# Backplane_Reference.net
KiCad netlist of a schematic drawn in EAGLE
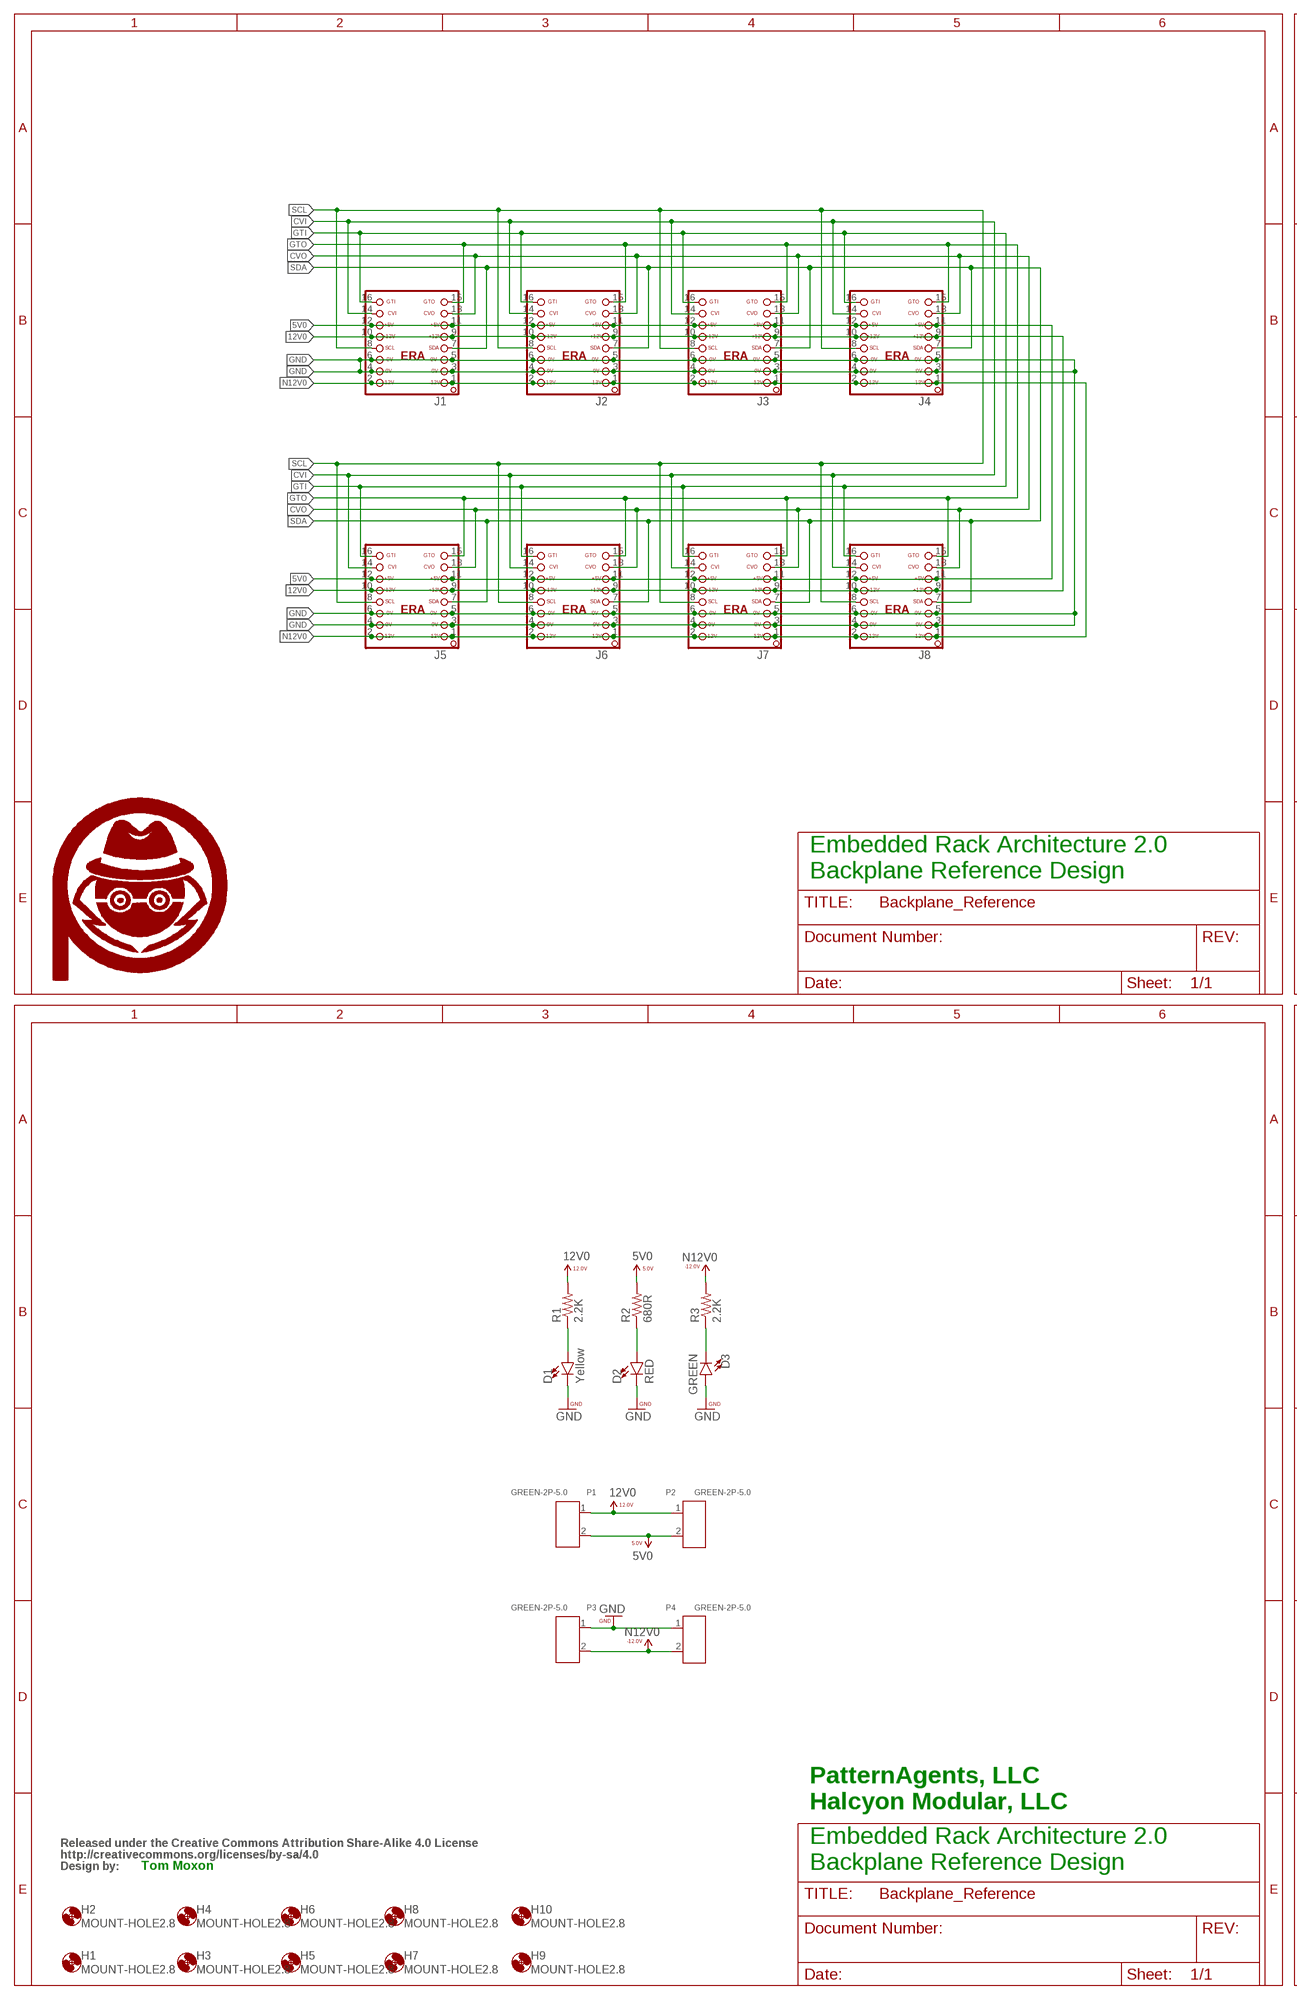
[diagram p0: schematic, sheet 1, part 1 of 2]
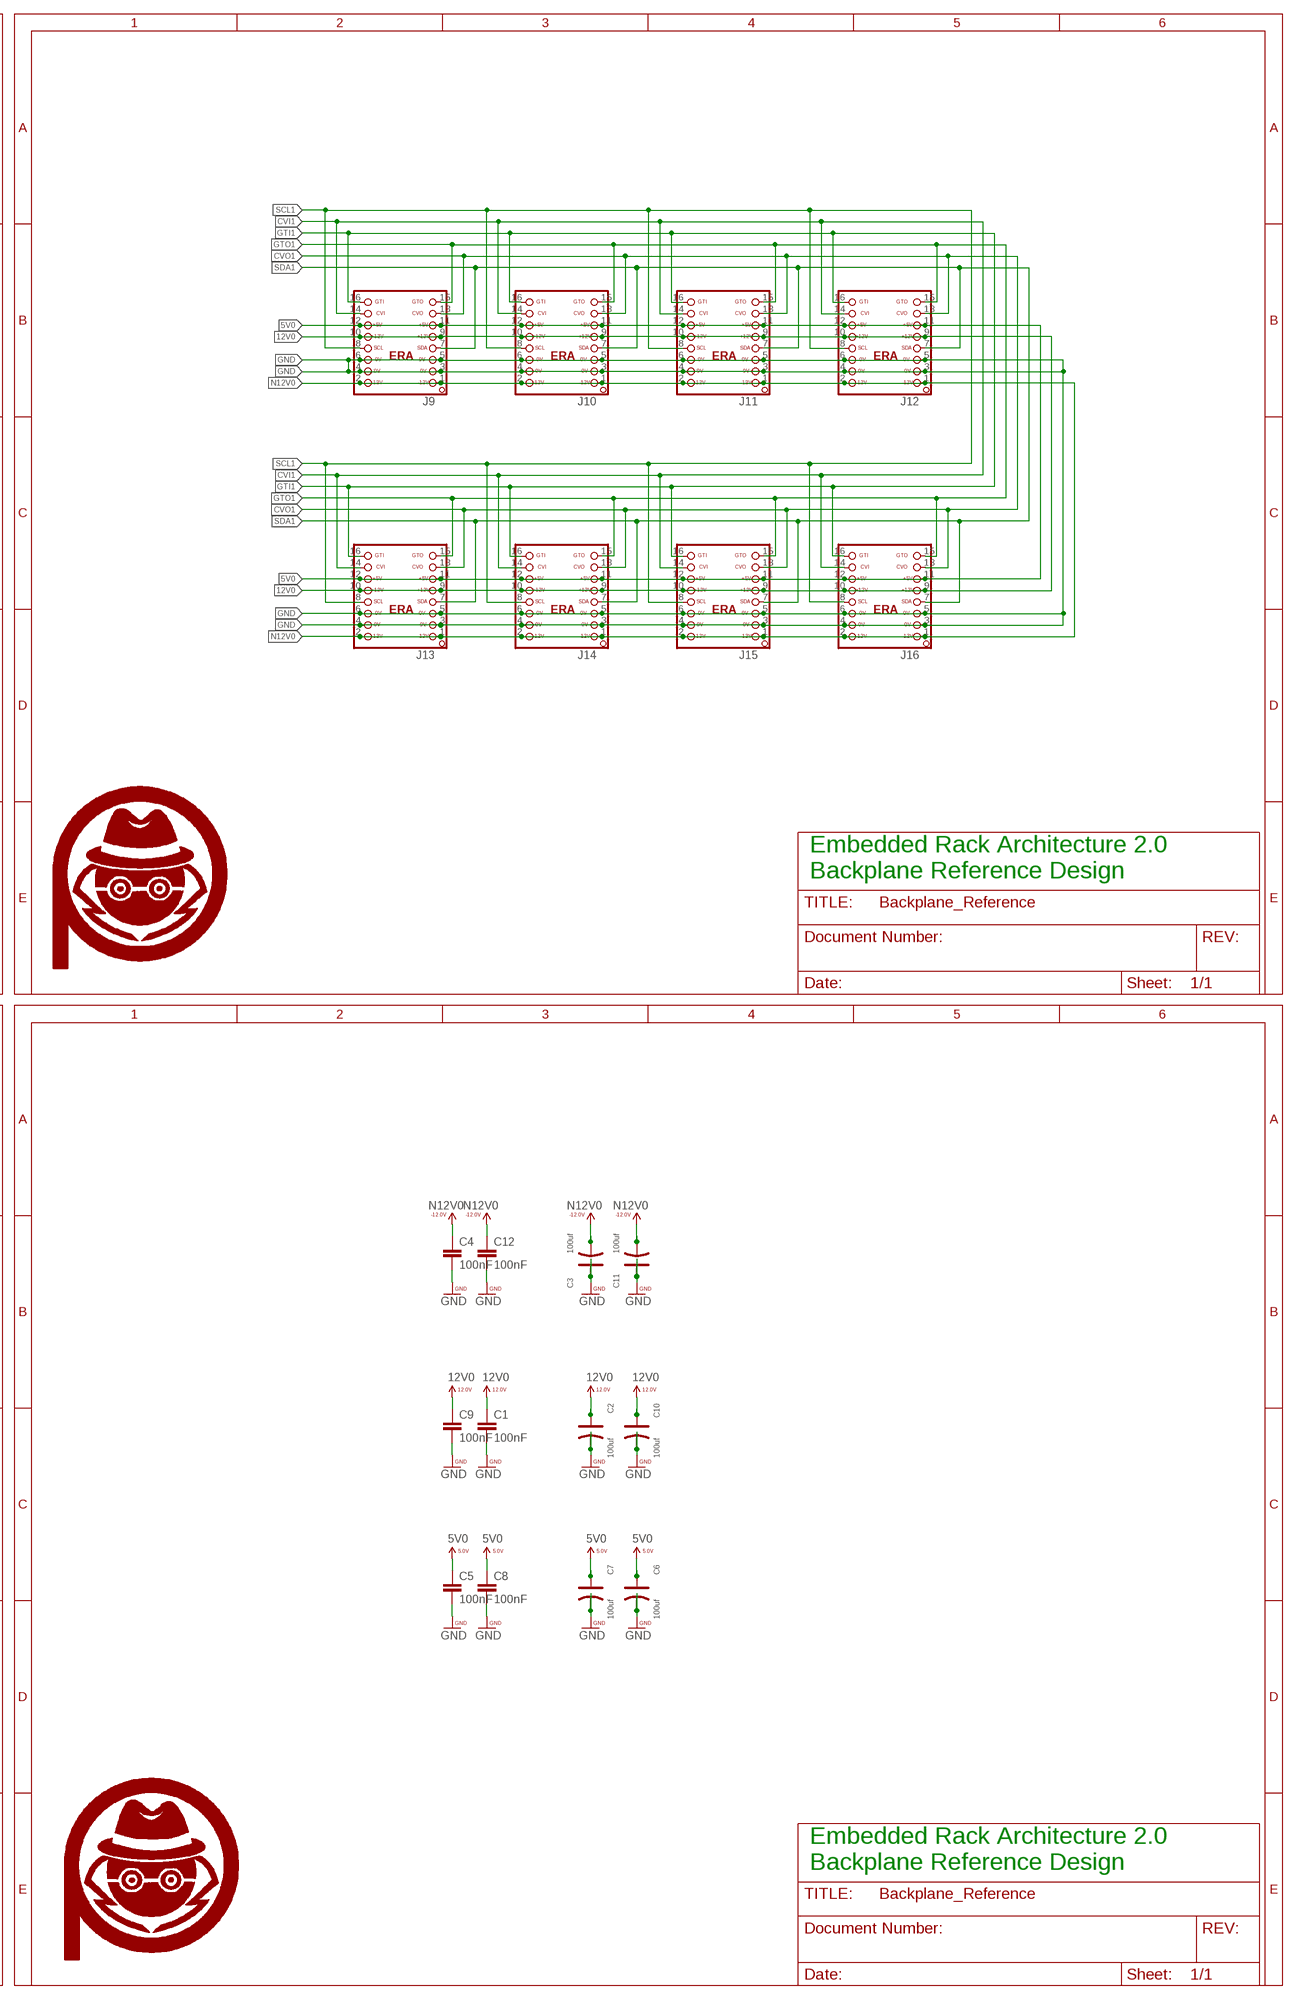
[diagram p1: schematic, sheet 1, part 2 of 2]

(export (version "E")
  (design (tool "Eeschema 10.0.6"))
  (components
    (comp (ref "C1")
      (value "100nF")
      (footprint "eagle-import:0603-CAP")
      (libsource (lib "eagle-import") (part "CAP0603-CAP"))
    )
    (comp (ref "C2")
      (value "100uf")
      (footprint "eagle-import:PC-D5.3MM")
      (fields (field (name "MPN") "KS 100uF/16V"))
      (libsource (lib "eagle-import") (part "DIP-ALUMINUM-100UF-16V(D5-H7MM)"))
    )
    (comp (ref "C3")
      (value "100uf")
      (footprint "eagle-import:PC-D5.3MM")
      (fields (field (name "MPN") "KS 100uF/16V"))
      (libsource (lib "eagle-import") (part "DIP-ALUMINUM-100UF-16V(D5-H7MM)"))
    )
    (comp (ref "C4")
      (value "100nF")
      (footprint "eagle-import:0603-CAP")
      (libsource (lib "eagle-import") (part "CAP0603-CAP"))
    )
    (comp (ref "C5")
      (value "100nF")
      (footprint "eagle-import:0603-CAP")
      (libsource (lib "eagle-import") (part "CAP0603-CAP"))
    )
    (comp (ref "C6")
      (value "100uf")
      (footprint "eagle-import:PC-D5.3MM")
      (fields (field (name "MPN") "KS 100uF/16V"))
      (libsource (lib "eagle-import") (part "DIP-ALUMINUM-100UF-16V(D5-H7MM)"))
    )
    (comp (ref "C7")
      (value "100uf")
      (footprint "eagle-import:PC-D5.3MM")
      (fields (field (name "MPN") "KS 100uF/16V"))
      (libsource (lib "eagle-import") (part "DIP-ALUMINUM-100UF-16V(D5-H7MM)"))
    )
    (comp (ref "C8")
      (value "100nF")
      (footprint "eagle-import:0603-CAP")
      (libsource (lib "eagle-import") (part "CAP0603-CAP"))
    )
    (comp (ref "C9")
      (value "100nF")
      (footprint "eagle-import:0603-CAP")
      (libsource (lib "eagle-import") (part "CAP0603-CAP"))
    )
    (comp (ref "C10")
      (value "100uf")
      (footprint "eagle-import:PC-D5.3MM")
      (fields (field (name "MPN") "KS 100uF/16V"))
      (libsource (lib "eagle-import") (part "DIP-ALUMINUM-100UF-16V(D5-H7MM)"))
    )
    (comp (ref "C11")
      (value "100uf")
      (footprint "eagle-import:PC-D5.3MM")
      (fields (field (name "MPN") "KS 100uF/16V"))
      (libsource (lib "eagle-import") (part "DIP-ALUMINUM-100UF-16V(D5-H7MM)"))
    )
    (comp (ref "C12")
      (value "100nF")
      (footprint "eagle-import:0603-CAP")
      (libsource (lib "eagle-import") (part "CAP0603-CAP"))
    )
    (comp (ref "D1")
      (value "Yellow")
      (footprint "eagle-import:LED-0603")
      (libsource (lib "eagle-import") (part "LED-YELLOW0603"))
    )
    (comp (ref "D2")
      (value "RED")
      (footprint "eagle-import:LED-0603")
      (libsource (lib "eagle-import") (part "LED-RED0603"))
    )
    (comp (ref "D3")
      (value "GREEN")
      (footprint "eagle-import:LED-0603")
      (libsource (lib "eagle-import") (part "LED-GREEN0603"))
    )
    (comp (ref "H1")
      (value "MOUNT-HOLE2.8")
      (footprint "eagle-import:2,8")
      (libsource (lib "eagle-import") (part "MOUNT-HOLE2.8"))
    )
    (comp (ref "H2")
      (value "MOUNT-HOLE2.8")
      (footprint "eagle-import:2,8")
      (libsource (lib "eagle-import") (part "MOUNT-HOLE2.8"))
    )
    (comp (ref "H3")
      (value "MOUNT-HOLE2.8")
      (footprint "eagle-import:2,8")
      (libsource (lib "eagle-import") (part "MOUNT-HOLE2.8"))
    )
    (comp (ref "H4")
      (value "MOUNT-HOLE2.8")
      (footprint "eagle-import:2,8")
      (libsource (lib "eagle-import") (part "MOUNT-HOLE2.8"))
    )
    (comp (ref "H5")
      (value "MOUNT-HOLE2.8")
      (footprint "eagle-import:2,8")
      (libsource (lib "eagle-import") (part "MOUNT-HOLE2.8"))
    )
    (comp (ref "H6")
      (value "MOUNT-HOLE2.8")
      (footprint "eagle-import:2,8")
      (libsource (lib "eagle-import") (part "MOUNT-HOLE2.8"))
    )
    (comp (ref "H7")
      (value "MOUNT-HOLE2.8")
      (footprint "eagle-import:2,8")
      (libsource (lib "eagle-import") (part "MOUNT-HOLE2.8"))
    )
    (comp (ref "H8")
      (value "MOUNT-HOLE2.8")
      (footprint "eagle-import:2,8")
      (libsource (lib "eagle-import") (part "MOUNT-HOLE2.8"))
    )
    (comp (ref "H9")
      (value "MOUNT-HOLE2.8")
      (footprint "eagle-import:2,8")
      (libsource (lib "eagle-import") (part "MOUNT-HOLE2.8"))
    )
    (comp (ref "H10")
      (value "MOUNT-HOLE2.8")
      (footprint "eagle-import:2,8")
      (libsource (lib "eagle-import") (part "MOUNT-HOLE2.8"))
    )
    (comp (ref "J1")
      (value "ERA-SHROUD")
      (footprint "eagle-import:ERA")
      (libsource (lib "eagle-import") (part "ERA-SHROUD"))
    )
    (comp (ref "J2")
      (value "ERA-SHROUD")
      (footprint "eagle-import:ERA")
      (libsource (lib "eagle-import") (part "ERA-SHROUD"))
    )
    (comp (ref "J3")
      (value "ERA-SHROUD")
      (footprint "eagle-import:ERA")
      (libsource (lib "eagle-import") (part "ERA-SHROUD"))
    )
    (comp (ref "J4")
      (value "ERA-SHROUD")
      (footprint "eagle-import:ERA")
      (libsource (lib "eagle-import") (part "ERA-SHROUD"))
    )
    (comp (ref "J5")
      (value "ERA-SHROUD")
      (footprint "eagle-import:ERA")
      (libsource (lib "eagle-import") (part "ERA-SHROUD"))
    )
    (comp (ref "J6")
      (value "ERA-SHROUD")
      (footprint "eagle-import:ERA")
      (libsource (lib "eagle-import") (part "ERA-SHROUD"))
    )
    (comp (ref "J7")
      (value "ERA-SHROUD")
      (footprint "eagle-import:ERA")
      (libsource (lib "eagle-import") (part "ERA-SHROUD"))
    )
    (comp (ref "J8")
      (value "ERA-SHROUD")
      (footprint "eagle-import:ERA")
      (libsource (lib "eagle-import") (part "ERA-SHROUD"))
    )
    (comp (ref "J9")
      (value "ERA-SHROUD")
      (footprint "eagle-import:ERA")
      (libsource (lib "eagle-import") (part "ERA-SHROUD"))
    )
    (comp (ref "J10")
      (value "ERA-SHROUD")
      (footprint "eagle-import:ERA")
      (libsource (lib "eagle-import") (part "ERA-SHROUD"))
    )
    (comp (ref "J11")
      (value "ERA-SHROUD")
      (footprint "eagle-import:ERA")
      (libsource (lib "eagle-import") (part "ERA-SHROUD"))
    )
    (comp (ref "J12")
      (value "ERA-SHROUD")
      (footprint "eagle-import:ERA")
      (libsource (lib "eagle-import") (part "ERA-SHROUD"))
    )
    (comp (ref "J13")
      (value "ERA-SHROUD")
      (footprint "eagle-import:ERA")
      (libsource (lib "eagle-import") (part "ERA-SHROUD"))
    )
    (comp (ref "J14")
      (value "ERA-SHROUD")
      (footprint "eagle-import:ERA")
      (libsource (lib "eagle-import") (part "ERA-SHROUD"))
    )
    (comp (ref "J15")
      (value "ERA-SHROUD")
      (footprint "eagle-import:ERA")
      (libsource (lib "eagle-import") (part "ERA-SHROUD"))
    )
    (comp (ref "J16")
      (value "ERA-SHROUD")
      (footprint "eagle-import:ERA")
      (libsource (lib "eagle-import") (part "ERA-SHROUD"))
    )
    (comp (ref "P1")
      (value "GREEN-2P-5.0")
      (footprint "eagle-import:H2-5.0-10.5X8.0MM")
      (libsource (lib "eagle-import") (part "SCREW-TERMINAL-GREEN(2P-5.0)"))
    )
    (comp (ref "P2")
      (value "GREEN-2P-5.0")
      (footprint "eagle-import:H2-5.0-10.5X8.0MM")
      (libsource (lib "eagle-import") (part "SCREW-TERMINAL-GREEN(2P-5.0)"))
    )
    (comp (ref "P3")
      (value "GREEN-2P-5.0")
      (footprint "eagle-import:H2-5.0-10.5X8.0MM")
      (libsource (lib "eagle-import") (part "SCREW-TERMINAL-GREEN(2P-5.0)"))
    )
    (comp (ref "P4")
      (value "GREEN-2P-5.0")
      (footprint "eagle-import:H2-5.0-10.5X8.0MM")
      (libsource (lib "eagle-import") (part "SCREW-TERMINAL-GREEN(2P-5.0)"))
    )
    (comp (ref "R1")
      (value "2.2K")
      (footprint "eagle-import:0603-RES")
      (libsource (lib "eagle-import") (part "RESISTOR0603"))
    )
    (comp (ref "R2")
      (value "680R")
      (footprint "eagle-import:0603-RES")
      (libsource (lib "eagle-import") (part "RESISTOR0603"))
    )
    (comp (ref "R3")
      (value "2.2K")
      (footprint "eagle-import:0603-RES")
      (libsource (lib "eagle-import") (part "RESISTOR0603"))
    )
    (comp (ref "U$19")
      (value "PA_LOGO_SYMMED")
      (footprint "eagle-import:PA_LOGO_AGENT_MED_SYM")
      (libsource (lib "eagle-import") (part "PA_LOGO_SYMMED"))
    )
    (comp (ref "U$37")
      (value "PA_LOGO_SYMMED")
      (footprint "eagle-import:PA_LOGO_AGENT_MED_SYM")
      (libsource (lib "eagle-import") (part "PA_LOGO_SYMMED"))
    )
    (comp (ref "U$38")
      (value "PA_LOGO_SYMLARGE")
      (footprint "eagle-import:PA_LOGO_AGENT_LRG_SYM")
      (libsource (lib "eagle-import") (part "PA_LOGO_SYMLARGE"))
    )
    (comp (ref "U$48")
      (value "BY_CC_SA_TEXTTEXT")
      (footprint "eagle-import:BY_CC_SA_TEXT")
      (libsource (lib "eagle-import") (part "BY_CC_SA_TEXTTEXT"))
    )
  )
  (nets
    (net (code "1") (name "5V0") (class "Default")
      (node (ref "C5") (pin "1") (pinfunction "1_1") (pintype "passive"))
      (node (ref "C6") (pin "+") (pinfunction "+_+") (pintype "passive"))
      (node (ref "C7") (pin "+") (pinfunction "+_+") (pintype "passive"))
      (node (ref "C8") (pin "1") (pinfunction "1_1") (pintype "passive"))
      (node (ref "J1") (pin "11") (pinfunction "11_11") (pintype "passive"))
      (node (ref "J1") (pin "12") (pinfunction "12_12") (pintype "passive"))
      (node (ref "J10") (pin "11") (pinfunction "11_11") (pintype "passive"))
      (node (ref "J10") (pin "12") (pinfunction "12_12") (pintype "passive"))
      (node (ref "J11") (pin "11") (pinfunction "11_11") (pintype "passive"))
      (node (ref "J11") (pin "12") (pinfunction "12_12") (pintype "passive"))
      (node (ref "J12") (pin "11") (pinfunction "11_11") (pintype "passive"))
      (node (ref "J12") (pin "12") (pinfunction "12_12") (pintype "passive"))
      (node (ref "J13") (pin "11") (pinfunction "11_11") (pintype "passive"))
      (node (ref "J13") (pin "12") (pinfunction "12_12") (pintype "passive"))
      (node (ref "J14") (pin "11") (pinfunction "11_11") (pintype "passive"))
      (node (ref "J14") (pin "12") (pinfunction "12_12") (pintype "passive"))
      (node (ref "J15") (pin "11") (pinfunction "11_11") (pintype "passive"))
      (node (ref "J15") (pin "12") (pinfunction "12_12") (pintype "passive"))
      (node (ref "J16") (pin "11") (pinfunction "11_11") (pintype "passive"))
      (node (ref "J16") (pin "12") (pinfunction "12_12") (pintype "passive"))
      (node (ref "J2") (pin "11") (pinfunction "11_11") (pintype "passive"))
      (node (ref "J2") (pin "12") (pinfunction "12_12") (pintype "passive"))
      (node (ref "J3") (pin "11") (pinfunction "11_11") (pintype "passive"))
      (node (ref "J3") (pin "12") (pinfunction "12_12") (pintype "passive"))
      (node (ref "J4") (pin "11") (pinfunction "11_11") (pintype "passive"))
      (node (ref "J4") (pin "12") (pinfunction "12_12") (pintype "passive"))
      (node (ref "J5") (pin "11") (pinfunction "11_11") (pintype "passive"))
      (node (ref "J5") (pin "12") (pinfunction "12_12") (pintype "passive"))
      (node (ref "J6") (pin "11") (pinfunction "11_11") (pintype "passive"))
      (node (ref "J6") (pin "12") (pinfunction "12_12") (pintype "passive"))
      (node (ref "J7") (pin "11") (pinfunction "11_11") (pintype "passive"))
      (node (ref "J7") (pin "12") (pinfunction "12_12") (pintype "passive"))
      (node (ref "J8") (pin "11") (pinfunction "11_11") (pintype "passive"))
      (node (ref "J8") (pin "12") (pinfunction "12_12") (pintype "passive"))
      (node (ref "J9") (pin "11") (pinfunction "11_11") (pintype "passive"))
      (node (ref "J9") (pin "12") (pinfunction "12_12") (pintype "passive"))
      (node (ref "P1") (pin "2") (pinfunction "2_2") (pintype "bidirectional"))
      (node (ref "P2") (pin "2") (pinfunction "2_2") (pintype "bidirectional"))
      (node (ref "R2") (pin "2") (pinfunction "2_2") (pintype "passive"))
    )
    (net (code "2") (name "12V0") (class "Default")
      (node (ref "C1") (pin "1") (pinfunction "1_1") (pintype "passive"))
      (node (ref "C10") (pin "+") (pinfunction "+_+") (pintype "passive"))
      (node (ref "C2") (pin "+") (pinfunction "+_+") (pintype "passive"))
      (node (ref "C9") (pin "1") (pinfunction "1_1") (pintype "passive"))
      (node (ref "J1") (pin "10") (pinfunction "10_10") (pintype "passive"))
      (node (ref "J1") (pin "9") (pinfunction "9_9") (pintype "passive"))
      (node (ref "J10") (pin "10") (pinfunction "10_10") (pintype "passive"))
      (node (ref "J10") (pin "9") (pinfunction "9_9") (pintype "passive"))
      (node (ref "J11") (pin "10") (pinfunction "10_10") (pintype "passive"))
      (node (ref "J11") (pin "9") (pinfunction "9_9") (pintype "passive"))
      (node (ref "J12") (pin "10") (pinfunction "10_10") (pintype "passive"))
      (node (ref "J12") (pin "9") (pinfunction "9_9") (pintype "passive"))
      (node (ref "J13") (pin "10") (pinfunction "10_10") (pintype "passive"))
      (node (ref "J13") (pin "9") (pinfunction "9_9") (pintype "passive"))
      (node (ref "J14") (pin "10") (pinfunction "10_10") (pintype "passive"))
      (node (ref "J14") (pin "9") (pinfunction "9_9") (pintype "passive"))
      (node (ref "J15") (pin "10") (pinfunction "10_10") (pintype "passive"))
      (node (ref "J15") (pin "9") (pinfunction "9_9") (pintype "passive"))
      (node (ref "J16") (pin "10") (pinfunction "10_10") (pintype "passive"))
      (node (ref "J16") (pin "9") (pinfunction "9_9") (pintype "passive"))
      (node (ref "J2") (pin "10") (pinfunction "10_10") (pintype "passive"))
      (node (ref "J2") (pin "9") (pinfunction "9_9") (pintype "passive"))
      (node (ref "J3") (pin "10") (pinfunction "10_10") (pintype "passive"))
      (node (ref "J3") (pin "9") (pinfunction "9_9") (pintype "passive"))
      (node (ref "J4") (pin "10") (pinfunction "10_10") (pintype "passive"))
      (node (ref "J4") (pin "9") (pinfunction "9_9") (pintype "passive"))
      (node (ref "J5") (pin "10") (pinfunction "10_10") (pintype "passive"))
      (node (ref "J5") (pin "9") (pinfunction "9_9") (pintype "passive"))
      (node (ref "J6") (pin "10") (pinfunction "10_10") (pintype "passive"))
      (node (ref "J6") (pin "9") (pinfunction "9_9") (pintype "passive"))
      (node (ref "J7") (pin "10") (pinfunction "10_10") (pintype "passive"))
      (node (ref "J7") (pin "9") (pinfunction "9_9") (pintype "passive"))
      (node (ref "J8") (pin "10") (pinfunction "10_10") (pintype "passive"))
      (node (ref "J8") (pin "9") (pinfunction "9_9") (pintype "passive"))
      (node (ref "J9") (pin "10") (pinfunction "10_10") (pintype "passive"))
      (node (ref "J9") (pin "9") (pinfunction "9_9") (pintype "passive"))
      (node (ref "P1") (pin "1") (pinfunction "1_1") (pintype "bidirectional"))
      (node (ref "P2") (pin "1") (pinfunction "1_1") (pintype "bidirectional"))
      (node (ref "R1") (pin "2") (pinfunction "2_2") (pintype "passive"))
    )
    (net (code "3") (name "CVI") (class "Default")
      (node (ref "J1") (pin "14") (pinfunction "14_14") (pintype "passive"))
      (node (ref "J2") (pin "14") (pinfunction "14_14") (pintype "passive"))
      (node (ref "J3") (pin "14") (pinfunction "14_14") (pintype "passive"))
      (node (ref "J4") (pin "14") (pinfunction "14_14") (pintype "passive"))
      (node (ref "J5") (pin "14") (pinfunction "14_14") (pintype "passive"))
      (node (ref "J6") (pin "14") (pinfunction "14_14") (pintype "passive"))
      (node (ref "J7") (pin "14") (pinfunction "14_14") (pintype "passive"))
      (node (ref "J8") (pin "14") (pinfunction "14_14") (pintype "passive"))
    )
    (net (code "4") (name "CVI1") (class "Default")
      (node (ref "J10") (pin "14") (pinfunction "14_14") (pintype "passive"))
      (node (ref "J11") (pin "14") (pinfunction "14_14") (pintype "passive"))
      (node (ref "J12") (pin "14") (pinfunction "14_14") (pintype "passive"))
      (node (ref "J13") (pin "14") (pinfunction "14_14") (pintype "passive"))
      (node (ref "J14") (pin "14") (pinfunction "14_14") (pintype "passive"))
      (node (ref "J15") (pin "14") (pinfunction "14_14") (pintype "passive"))
      (node (ref "J16") (pin "14") (pinfunction "14_14") (pintype "passive"))
      (node (ref "J9") (pin "14") (pinfunction "14_14") (pintype "passive"))
    )
    (net (code "5") (name "CVO") (class "Default")
      (node (ref "J1") (pin "13") (pinfunction "13_13") (pintype "passive"))
      (node (ref "J2") (pin "13") (pinfunction "13_13") (pintype "passive"))
      (node (ref "J3") (pin "13") (pinfunction "13_13") (pintype "passive"))
      (node (ref "J4") (pin "13") (pinfunction "13_13") (pintype "passive"))
      (node (ref "J5") (pin "13") (pinfunction "13_13") (pintype "passive"))
      (node (ref "J6") (pin "13") (pinfunction "13_13") (pintype "passive"))
      (node (ref "J7") (pin "13") (pinfunction "13_13") (pintype "passive"))
      (node (ref "J8") (pin "13") (pinfunction "13_13") (pintype "passive"))
    )
    (net (code "6") (name "CVO1") (class "Default")
      (node (ref "J10") (pin "13") (pinfunction "13_13") (pintype "passive"))
      (node (ref "J11") (pin "13") (pinfunction "13_13") (pintype "passive"))
      (node (ref "J12") (pin "13") (pinfunction "13_13") (pintype "passive"))
      (node (ref "J13") (pin "13") (pinfunction "13_13") (pintype "passive"))
      (node (ref "J14") (pin "13") (pinfunction "13_13") (pintype "passive"))
      (node (ref "J15") (pin "13") (pinfunction "13_13") (pintype "passive"))
      (node (ref "J16") (pin "13") (pinfunction "13_13") (pintype "passive"))
      (node (ref "J9") (pin "13") (pinfunction "13_13") (pintype "passive"))
    )
    (net (code "7") (name "GND") (class "Default")
      (node (ref "C1") (pin "2") (pinfunction "2_2") (pintype "passive"))
      (node (ref "C10") (pin "-") (pinfunction "-_-") (pintype "passive"))
      (node (ref "C11") (pin "+") (pinfunction "+_+") (pintype "passive"))
      (node (ref "C12") (pin "2") (pinfunction "2_2") (pintype "passive"))
      (node (ref "C2") (pin "-") (pinfunction "-_-") (pintype "passive"))
      (node (ref "C3") (pin "+") (pinfunction "+_+") (pintype "passive"))
      (node (ref "C4") (pin "2") (pinfunction "2_2") (pintype "passive"))
      (node (ref "C5") (pin "2") (pinfunction "2_2") (pintype "passive"))
      (node (ref "C6") (pin "-") (pinfunction "-_-") (pintype "passive"))
      (node (ref "C7") (pin "-") (pinfunction "-_-") (pintype "passive"))
      (node (ref "C8") (pin "2") (pinfunction "2_2") (pintype "passive"))
      (node (ref "C9") (pin "2") (pinfunction "2_2") (pintype "passive"))
      (node (ref "D1") (pin "C") (pinfunction "C_C") (pintype "passive"))
      (node (ref "D2") (pin "C") (pinfunction "C_C") (pintype "passive"))
      (node (ref "D3") (pin "A") (pinfunction "A_A") (pintype "passive"))
      (node (ref "J1") (pin "3") (pinfunction "3_3") (pintype "passive"))
      (node (ref "J1") (pin "4") (pinfunction "4_4") (pintype "passive"))
      (node (ref "J1") (pin "5") (pinfunction "5_5") (pintype "passive"))
      (node (ref "J1") (pin "6") (pinfunction "6_6") (pintype "passive"))
      (node (ref "J10") (pin "3") (pinfunction "3_3") (pintype "passive"))
      (node (ref "J10") (pin "4") (pinfunction "4_4") (pintype "passive"))
      (node (ref "J10") (pin "5") (pinfunction "5_5") (pintype "passive"))
      (node (ref "J10") (pin "6") (pinfunction "6_6") (pintype "passive"))
      (node (ref "J11") (pin "3") (pinfunction "3_3") (pintype "passive"))
      (node (ref "J11") (pin "4") (pinfunction "4_4") (pintype "passive"))
      (node (ref "J11") (pin "5") (pinfunction "5_5") (pintype "passive"))
      (node (ref "J11") (pin "6") (pinfunction "6_6") (pintype "passive"))
      (node (ref "J12") (pin "3") (pinfunction "3_3") (pintype "passive"))
      (node (ref "J12") (pin "4") (pinfunction "4_4") (pintype "passive"))
      (node (ref "J12") (pin "5") (pinfunction "5_5") (pintype "passive"))
      (node (ref "J12") (pin "6") (pinfunction "6_6") (pintype "passive"))
      (node (ref "J13") (pin "3") (pinfunction "3_3") (pintype "passive"))
      (node (ref "J13") (pin "4") (pinfunction "4_4") (pintype "passive"))
      (node (ref "J13") (pin "5") (pinfunction "5_5") (pintype "passive"))
      (node (ref "J13") (pin "6") (pinfunction "6_6") (pintype "passive"))
      (node (ref "J14") (pin "3") (pinfunction "3_3") (pintype "passive"))
      (node (ref "J14") (pin "4") (pinfunction "4_4") (pintype "passive"))
      (node (ref "J14") (pin "5") (pinfunction "5_5") (pintype "passive"))
      (node (ref "J14") (pin "6") (pinfunction "6_6") (pintype "passive"))
      (node (ref "J15") (pin "3") (pinfunction "3_3") (pintype "passive"))
      (node (ref "J15") (pin "4") (pinfunction "4_4") (pintype "passive"))
      (node (ref "J15") (pin "5") (pinfunction "5_5") (pintype "passive"))
      (node (ref "J15") (pin "6") (pinfunction "6_6") (pintype "passive"))
      (node (ref "J16") (pin "3") (pinfunction "3_3") (pintype "passive"))
      (node (ref "J16") (pin "4") (pinfunction "4_4") (pintype "passive"))
      (node (ref "J16") (pin "5") (pinfunction "5_5") (pintype "passive"))
      (node (ref "J16") (pin "6") (pinfunction "6_6") (pintype "passive"))
      (node (ref "J2") (pin "3") (pinfunction "3_3") (pintype "passive"))
      (node (ref "J2") (pin "4") (pinfunction "4_4") (pintype "passive"))
      (node (ref "J2") (pin "5") (pinfunction "5_5") (pintype "passive"))
      (node (ref "J2") (pin "6") (pinfunction "6_6") (pintype "passive"))
      (node (ref "J3") (pin "3") (pinfunction "3_3") (pintype "passive"))
      (node (ref "J3") (pin "4") (pinfunction "4_4") (pintype "passive"))
      (node (ref "J3") (pin "5") (pinfunction "5_5") (pintype "passive"))
      (node (ref "J3") (pin "6") (pinfunction "6_6") (pintype "passive"))
      (node (ref "J4") (pin "3") (pinfunction "3_3") (pintype "passive"))
      (node (ref "J4") (pin "4") (pinfunction "4_4") (pintype "passive"))
      (node (ref "J4") (pin "5") (pinfunction "5_5") (pintype "passive"))
      (node (ref "J4") (pin "6") (pinfunction "6_6") (pintype "passive"))
      (node (ref "J5") (pin "3") (pinfunction "3_3") (pintype "passive"))
      (node (ref "J5") (pin "4") (pinfunction "4_4") (pintype "passive"))
      (node (ref "J5") (pin "5") (pinfunction "5_5") (pintype "passive"))
      (node (ref "J5") (pin "6") (pinfunction "6_6") (pintype "passive"))
      (node (ref "J6") (pin "3") (pinfunction "3_3") (pintype "passive"))
      (node (ref "J6") (pin "4") (pinfunction "4_4") (pintype "passive"))
      (node (ref "J6") (pin "5") (pinfunction "5_5") (pintype "passive"))
      (node (ref "J6") (pin "6") (pinfunction "6_6") (pintype "passive"))
      (node (ref "J7") (pin "3") (pinfunction "3_3") (pintype "passive"))
      (node (ref "J7") (pin "4") (pinfunction "4_4") (pintype "passive"))
      (node (ref "J7") (pin "5") (pinfunction "5_5") (pintype "passive"))
      (node (ref "J7") (pin "6") (pinfunction "6_6") (pintype "passive"))
      (node (ref "J8") (pin "3") (pinfunction "3_3") (pintype "passive"))
      (node (ref "J8") (pin "4") (pinfunction "4_4") (pintype "passive"))
      (node (ref "J8") (pin "5") (pinfunction "5_5") (pintype "passive"))
      (node (ref "J8") (pin "6") (pinfunction "6_6") (pintype "passive"))
      (node (ref "J9") (pin "3") (pinfunction "3_3") (pintype "passive"))
      (node (ref "J9") (pin "4") (pinfunction "4_4") (pintype "passive"))
      (node (ref "J9") (pin "5") (pinfunction "5_5") (pintype "passive"))
      (node (ref "J9") (pin "6") (pinfunction "6_6") (pintype "passive"))
      (node (ref "P3") (pin "1") (pinfunction "1_1") (pintype "bidirectional"))
      (node (ref "P4") (pin "1") (pinfunction "1_1") (pintype "bidirectional"))
    )
    (net (code "8") (name "GTI") (class "Default")
      (node (ref "J1") (pin "16") (pinfunction "16_16") (pintype "passive"))
      (node (ref "J2") (pin "16") (pinfunction "16_16") (pintype "passive"))
      (node (ref "J3") (pin "16") (pinfunction "16_16") (pintype "passive"))
      (node (ref "J4") (pin "16") (pinfunction "16_16") (pintype "passive"))
      (node (ref "J5") (pin "16") (pinfunction "16_16") (pintype "passive"))
      (node (ref "J6") (pin "16") (pinfunction "16_16") (pintype "passive"))
      (node (ref "J7") (pin "16") (pinfunction "16_16") (pintype "passive"))
      (node (ref "J8") (pin "16") (pinfunction "16_16") (pintype "passive"))
    )
    (net (code "9") (name "GTI1") (class "Default")
      (node (ref "J10") (pin "16") (pinfunction "16_16") (pintype "passive"))
      (node (ref "J11") (pin "16") (pinfunction "16_16") (pintype "passive"))
      (node (ref "J12") (pin "16") (pinfunction "16_16") (pintype "passive"))
      (node (ref "J13") (pin "16") (pinfunction "16_16") (pintype "passive"))
      (node (ref "J14") (pin "16") (pinfunction "16_16") (pintype "passive"))
      (node (ref "J15") (pin "16") (pinfunction "16_16") (pintype "passive"))
      (node (ref "J16") (pin "16") (pinfunction "16_16") (pintype "passive"))
      (node (ref "J9") (pin "16") (pinfunction "16_16") (pintype "passive"))
    )
    (net (code "10") (name "GTO") (class "Default")
      (node (ref "J1") (pin "15") (pinfunction "15_15") (pintype "passive"))
      (node (ref "J2") (pin "15") (pinfunction "15_15") (pintype "passive"))
      (node (ref "J3") (pin "15") (pinfunction "15_15") (pintype "passive"))
      (node (ref "J4") (pin "15") (pinfunction "15_15") (pintype "passive"))
      (node (ref "J5") (pin "15") (pinfunction "15_15") (pintype "passive"))
      (node (ref "J6") (pin "15") (pinfunction "15_15") (pintype "passive"))
      (node (ref "J7") (pin "15") (pinfunction "15_15") (pintype "passive"))
      (node (ref "J8") (pin "15") (pinfunction "15_15") (pintype "passive"))
    )
    (net (code "11") (name "GTO1") (class "Default")
      (node (ref "J10") (pin "15") (pinfunction "15_15") (pintype "passive"))
      (node (ref "J11") (pin "15") (pinfunction "15_15") (pintype "passive"))
      (node (ref "J12") (pin "15") (pinfunction "15_15") (pintype "passive"))
      (node (ref "J13") (pin "15") (pinfunction "15_15") (pintype "passive"))
      (node (ref "J14") (pin "15") (pinfunction "15_15") (pintype "passive"))
      (node (ref "J15") (pin "15") (pinfunction "15_15") (pintype "passive"))
      (node (ref "J16") (pin "15") (pinfunction "15_15") (pintype "passive"))
      (node (ref "J9") (pin "15") (pinfunction "15_15") (pintype "passive"))
    )
    (net (code "12") (name "N12V0") (class "Default")
      (node (ref "C11") (pin "-") (pinfunction "-_-") (pintype "passive"))
      (node (ref "C12") (pin "1") (pinfunction "1_1") (pintype "passive"))
      (node (ref "C3") (pin "-") (pinfunction "-_-") (pintype "passive"))
      (node (ref "C4") (pin "1") (pinfunction "1_1") (pintype "passive"))
      (node (ref "J1") (pin "1") (pinfunction "1_1") (pintype "passive"))
      (node (ref "J1") (pin "2") (pinfunction "2_2") (pintype "passive"))
      (node (ref "J10") (pin "1") (pinfunction "1_1") (pintype "passive"))
      (node (ref "J10") (pin "2") (pinfunction "2_2") (pintype "passive"))
      (node (ref "J11") (pin "1") (pinfunction "1_1") (pintype "passive"))
      (node (ref "J11") (pin "2") (pinfunction "2_2") (pintype "passive"))
      (node (ref "J12") (pin "1") (pinfunction "1_1") (pintype "passive"))
      (node (ref "J12") (pin "2") (pinfunction "2_2") (pintype "passive"))
      (node (ref "J13") (pin "1") (pinfunction "1_1") (pintype "passive"))
      (node (ref "J13") (pin "2") (pinfunction "2_2") (pintype "passive"))
      (node (ref "J14") (pin "1") (pinfunction "1_1") (pintype "passive"))
      (node (ref "J14") (pin "2") (pinfunction "2_2") (pintype "passive"))
      (node (ref "J15") (pin "1") (pinfunction "1_1") (pintype "passive"))
      (node (ref "J15") (pin "2") (pinfunction "2_2") (pintype "passive"))
      (node (ref "J16") (pin "1") (pinfunction "1_1") (pintype "passive"))
      (node (ref "J16") (pin "2") (pinfunction "2_2") (pintype "passive"))
      (node (ref "J2") (pin "1") (pinfunction "1_1") (pintype "passive"))
      (node (ref "J2") (pin "2") (pinfunction "2_2") (pintype "passive"))
      (node (ref "J3") (pin "1") (pinfunction "1_1") (pintype "passive"))
      (node (ref "J3") (pin "2") (pinfunction "2_2") (pintype "passive"))
      (node (ref "J4") (pin "1") (pinfunction "1_1") (pintype "passive"))
      (node (ref "J4") (pin "2") (pinfunction "2_2") (pintype "passive"))
      (node (ref "J5") (pin "1") (pinfunction "1_1") (pintype "passive"))
      (node (ref "J5") (pin "2") (pinfunction "2_2") (pintype "passive"))
      (node (ref "J6") (pin "1") (pinfunction "1_1") (pintype "passive"))
      (node (ref "J6") (pin "2") (pinfunction "2_2") (pintype "passive"))
      (node (ref "J7") (pin "1") (pinfunction "1_1") (pintype "passive"))
      (node (ref "J7") (pin "2") (pinfunction "2_2") (pintype "passive"))
      (node (ref "J8") (pin "1") (pinfunction "1_1") (pintype "passive"))
      (node (ref "J8") (pin "2") (pinfunction "2_2") (pintype "passive"))
      (node (ref "J9") (pin "1") (pinfunction "1_1") (pintype "passive"))
      (node (ref "J9") (pin "2") (pinfunction "2_2") (pintype "passive"))
      (node (ref "P3") (pin "2") (pinfunction "2_2") (pintype "bidirectional"))
      (node (ref "P4") (pin "2") (pinfunction "2_2") (pintype "bidirectional"))
      (node (ref "R3") (pin "2") (pinfunction "2_2") (pintype "passive"))
    )
    (net (code "13") (name "Net-(D1-PadA)") (class "Default")
      (node (ref "D1") (pin "A") (pinfunction "A_A") (pintype "passive"))
      (node (ref "R1") (pin "1") (pinfunction "1_1") (pintype "passive"))
    )
    (net (code "14") (name "Net-(D2-PadA)") (class "Default")
      (node (ref "D2") (pin "A") (pinfunction "A_A") (pintype "passive"))
      (node (ref "R2") (pin "1") (pinfunction "1_1") (pintype "passive"))
    )
    (net (code "15") (name "Net-(D3-PadC)") (class "Default")
      (node (ref "D3") (pin "C") (pinfunction "C_C") (pintype "passive"))
      (node (ref "R3") (pin "1") (pinfunction "1_1") (pintype "passive"))
    )
    (net (code "16") (name "SCL") (class "Default")
      (node (ref "J1") (pin "8") (pinfunction "8_8") (pintype "passive"))
      (node (ref "J2") (pin "8") (pinfunction "8_8") (pintype "passive"))
      (node (ref "J3") (pin "8") (pinfunction "8_8") (pintype "passive"))
      (node (ref "J4") (pin "8") (pinfunction "8_8") (pintype "passive"))
      (node (ref "J5") (pin "8") (pinfunction "8_8") (pintype "passive"))
      (node (ref "J6") (pin "8") (pinfunction "8_8") (pintype "passive"))
      (node (ref "J7") (pin "8") (pinfunction "8_8") (pintype "passive"))
      (node (ref "J8") (pin "8") (pinfunction "8_8") (pintype "passive"))
    )
    (net (code "17") (name "SCL1") (class "Default")
      (node (ref "J10") (pin "8") (pinfunction "8_8") (pintype "passive"))
      (node (ref "J11") (pin "8") (pinfunction "8_8") (pintype "passive"))
      (node (ref "J12") (pin "8") (pinfunction "8_8") (pintype "passive"))
      (node (ref "J13") (pin "8") (pinfunction "8_8") (pintype "passive"))
      (node (ref "J14") (pin "8") (pinfunction "8_8") (pintype "passive"))
      (node (ref "J15") (pin "8") (pinfunction "8_8") (pintype "passive"))
      (node (ref "J16") (pin "8") (pinfunction "8_8") (pintype "passive"))
      (node (ref "J9") (pin "8") (pinfunction "8_8") (pintype "passive"))
    )
    (net (code "18") (name "SDA") (class "Default")
      (node (ref "J1") (pin "7") (pinfunction "7_7") (pintype "passive"))
      (node (ref "J2") (pin "7") (pinfunction "7_7") (pintype "passive"))
      (node (ref "J3") (pin "7") (pinfunction "7_7") (pintype "passive"))
      (node (ref "J4") (pin "7") (pinfunction "7_7") (pintype "passive"))
      (node (ref "J5") (pin "7") (pinfunction "7_7") (pintype "passive"))
      (node (ref "J6") (pin "7") (pinfunction "7_7") (pintype "passive"))
      (node (ref "J7") (pin "7") (pinfunction "7_7") (pintype "passive"))
      (node (ref "J8") (pin "7") (pinfunction "7_7") (pintype "passive"))
    )
    (net (code "19") (name "SDA1") (class "Default")
      (node (ref "J10") (pin "7") (pinfunction "7_7") (pintype "passive"))
      (node (ref "J11") (pin "7") (pinfunction "7_7") (pintype "passive"))
      (node (ref "J12") (pin "7") (pinfunction "7_7") (pintype "passive"))
      (node (ref "J13") (pin "7") (pinfunction "7_7") (pintype "passive"))
      (node (ref "J14") (pin "7") (pinfunction "7_7") (pintype "passive"))
      (node (ref "J15") (pin "7") (pinfunction "7_7") (pintype "passive"))
      (node (ref "J16") (pin "7") (pinfunction "7_7") (pintype "passive"))
      (node (ref "J9") (pin "7") (pinfunction "7_7") (pintype "passive"))
    )
  )
)
